# CS301_YOURGROUPNUM.net
KiCad netlist of a schematic drawn in Altium Designer
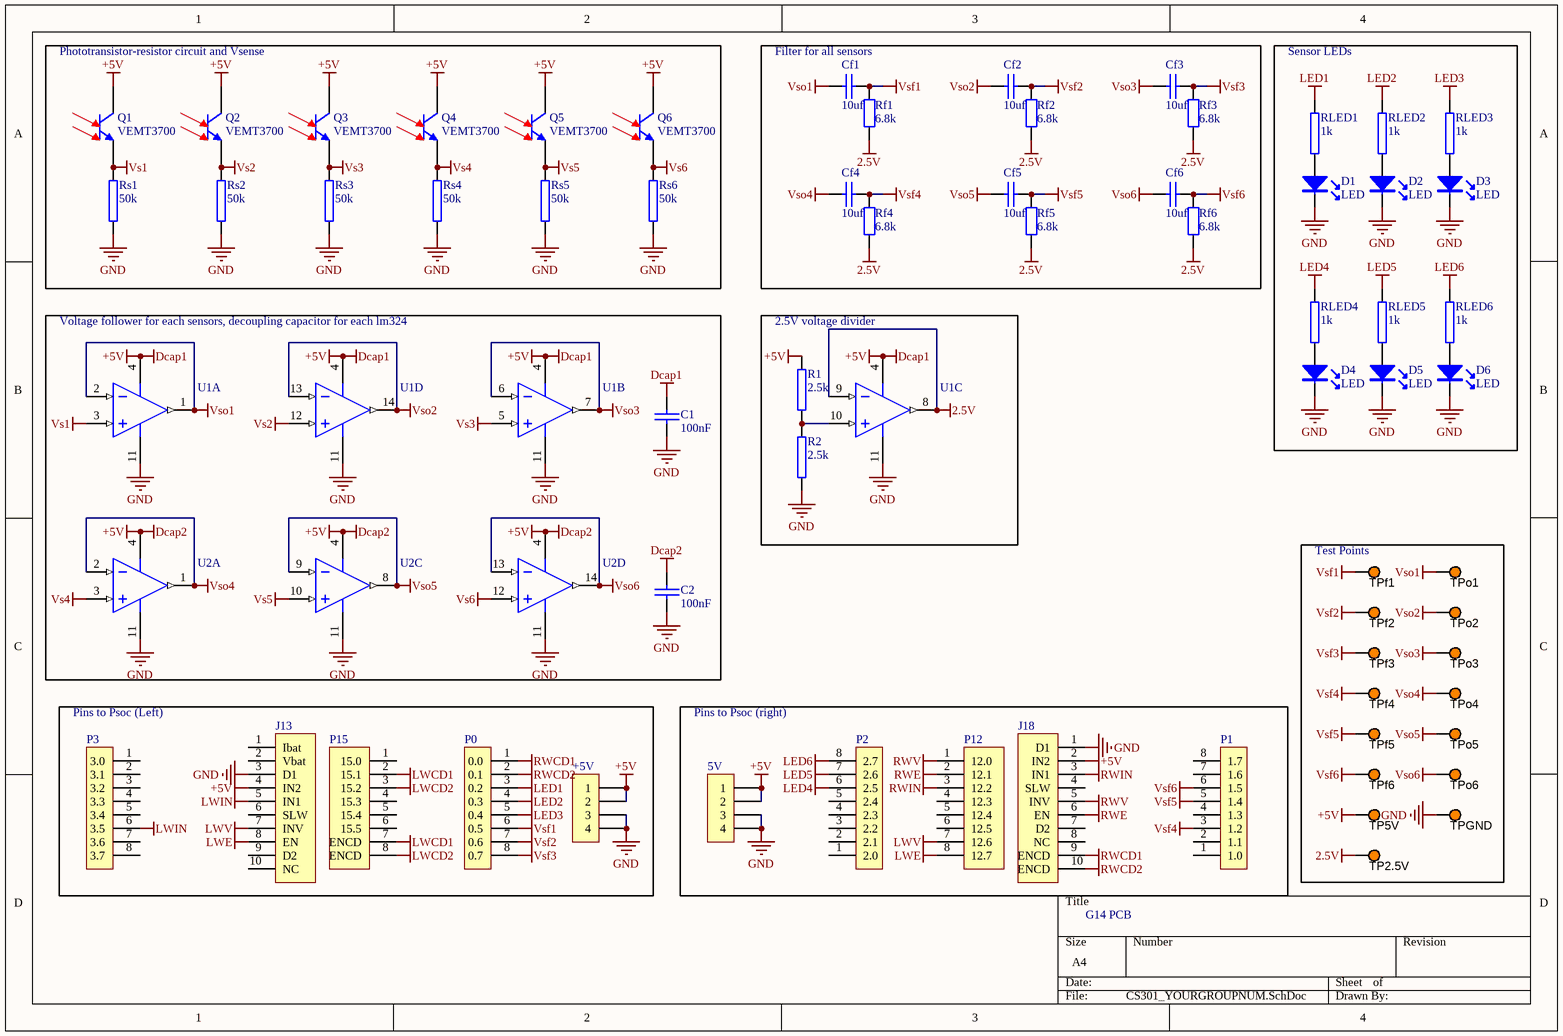
[diagram p0: CS301_YOURGROUPNUM.SchDoc]

(export (version "E")
  (design (tool "Eeschema 10.0.6"))
  (components
    (comp (ref "+5V")
      (value "5V")
      (footprint "IDC4")
      (description "Connector")
      (libsource (lib "Miscellaneous Devices") (part "CON4"))
    )
    (comp (ref "5V")
      (value "5V")
      (footprint "IDC4")
      (description "Connector")
      (libsource (lib "Miscellaneous Devices") (part "CON4"))
    )
    (comp (ref "C1")
      (value "100nF")
      (footprint "CCAP-5P0")
      (description "TH ceramic capacitor with 5mm pitch")
      (libsource (lib "EE209_SchLib") (part "CerCap_TH_5P0"))
    )
    (comp (ref "C2")
      (value "100nF")
      (footprint "CCAP-5P0")
      (description "TH ceramic capacitor with 5mm pitch")
      (libsource (lib "EE209_SchLib") (part "CerCap_TH_5P0"))
    )
    (comp (ref "Cf1")
      (value "10uf")
      (footprint "CCAP-5P0")
      (description "TH ceramic capacitor with 5mm pitch")
      (libsource (lib "EE209_SchLib") (part "CerCap_TH_5P0"))
    )
    (comp (ref "Cf2")
      (value "10uf")
      (footprint "CCAP-5P0")
      (description "TH ceramic capacitor with 5mm pitch")
      (libsource (lib "EE209_SchLib") (part "CerCap_TH_5P0"))
    )
    (comp (ref "Cf3")
      (value "10uf")
      (footprint "CCAP-5P0")
      (description "TH ceramic capacitor with 5mm pitch")
      (libsource (lib "EE209_SchLib") (part "CerCap_TH_5P0"))
    )
    (comp (ref "Cf4")
      (value "10uf")
      (footprint "CCAP-5P0")
      (description "TH ceramic capacitor with 5mm pitch")
      (libsource (lib "EE209_SchLib") (part "CerCap_TH_5P0"))
    )
    (comp (ref "Cf5")
      (value "10uf")
      (footprint "CCAP-5P0")
      (description "TH ceramic capacitor with 5mm pitch")
      (libsource (lib "EE209_SchLib") (part "CerCap_TH_5P0"))
    )
    (comp (ref "Cf6")
      (value "10uf")
      (footprint "CCAP-5P0")
      (description "TH ceramic capacitor with 5mm pitch")
      (libsource (lib "EE209_SchLib") (part "CerCap_TH_5P0"))
    )
    (comp (ref "D1") (value "LED") (footprint "LED0.1/5MM") (libsource (lib "COMSYS301") (part "LED")))
    (comp (ref "D2") (value "LED") (footprint "LED0.1/5MM") (libsource (lib "COMSYS301") (part "LED")))
    (comp (ref "D3") (value "LED") (footprint "LED0.1/5MM") (libsource (lib "COMSYS301") (part "LED")))
    (comp (ref "D4") (value "LED") (footprint "LED0.1/5MM") (libsource (lib "COMSYS301") (part "LED")))
    (comp (ref "D5") (value "LED") (footprint "LED0.1/5MM") (libsource (lib "COMSYS301") (part "LED")))
    (comp (ref "D6") (value "LED") (footprint "LED0.1/5MM") (libsource (lib "COMSYS301") (part "LED")))
    (comp (ref "J13")
      (value "CON10")
      (footprint "idc10")
      (description "Connector")
      (libsource (lib "Miscellaneous Devices") (part "CON10"))
    )
    (comp (ref "J18")
      (value "CON10")
      (footprint "IDC10")
      (description "Connector")
      (libsource (lib "") (part "CON10_1"))
    )
    (comp (ref "P0")
      (value "P0")
      (footprint "idc8")
      (description "Connector")
      (libsource (lib "") (part "CON8_2"))
    )
    (comp (ref "P1")
      (value "P1")
      (footprint "idc8")
      (description "Connector")
      (libsource (lib "") (part "CON8_1"))
    )
    (comp (ref "P2")
      (value "P2")
      (footprint "idc8")
      (description "Connector")
      (libsource (lib "Miscellaneous Devices") (part "CON8"))
    )
    (comp (ref "P3")
      (value "P3")
      (footprint "idc8")
      (description "Connector")
      (libsource (lib "") (part "CON8_2"))
    )
    (comp (ref "P12")
      (value "P12")
      (footprint "idc8")
      (description "Connector")
      (libsource (lib "Miscellaneous Devices") (part "CON8_1"))
    )
    (comp (ref "P15")
      (value "P15")
      (footprint "idc8")
      (description "Connector")
      (libsource (lib "") (part "CON8_1_1"))
    )
    (comp (ref "Q1")
      (value "VEMT3700")
      (footprint "VEMT3700")
      (description "Silicon NPN Phototransistor")
      (libsource (lib "COMSYS301") (part "VEMT3700"))
    )
    (comp (ref "Q2")
      (value "VEMT3700")
      (footprint "VEMT3700")
      (description "Silicon NPN Phototransistor")
      (libsource (lib "COMSYS301") (part "VEMT3700"))
    )
    (comp (ref "Q3")
      (value "VEMT3700")
      (footprint "VEMT3700")
      (description "Silicon NPN Phototransistor")
      (libsource (lib "COMSYS301") (part "VEMT3700"))
    )
    (comp (ref "Q4")
      (value "VEMT3700")
      (footprint "VEMT3700")
      (description "Silicon NPN Phototransistor")
      (libsource (lib "COMSYS301") (part "VEMT3700"))
    )
    (comp (ref "Q5")
      (value "VEMT3700")
      (footprint "VEMT3700")
      (description "Silicon NPN Phototransistor")
      (libsource (lib "COMSYS301") (part "VEMT3700"))
    )
    (comp (ref "Q6")
      (value "VEMT3700")
      (footprint "VEMT3700")
      (description "Silicon NPN Phototransistor")
      (libsource (lib "COMSYS301") (part "VEMT3700"))
    )
    (comp (ref "R1") (value "2.5k") (footprint "AXIAL0.4") (libsource (lib "COMSYS301") (part "RES2")))
    (comp (ref "R2") (value "2.5k") (footprint "AXIAL0.4") (libsource (lib "COMSYS301") (part "RES2")))
    (comp (ref "Rf1")
      (value "6.8k")
      (footprint "AXIAL-0.4")
      (description "Through hole resistor")
      (fields (field (name "PUBLISHER") "Altium Limited"))
      (libsource (lib "EE209_SchLib") (part "Res_TH_0AX4"))
    )
    (comp (ref "Rf2")
      (value "6.8k")
      (footprint "AXIAL-0.4")
      (description "Through hole resistor")
      (fields (field (name "PUBLISHER") "Altium Limited"))
      (libsource (lib "EE209_SchLib") (part "Res_TH_0AX4"))
    )
    (comp (ref "Rf3")
      (value "6.8k")
      (footprint "AXIAL-0.4")
      (description "Through hole resistor")
      (fields (field (name "PUBLISHER") "Altium Limited"))
      (libsource (lib "EE209_SchLib") (part "Res_TH_0AX4"))
    )
    (comp (ref "Rf4")
      (value "6.8k")
      (footprint "AXIAL-0.4")
      (description "Through hole resistor")
      (fields (field (name "PUBLISHER") "Altium Limited"))
      (libsource (lib "EE209_SchLib") (part "Res_TH_0AX4"))
    )
    (comp (ref "Rf5")
      (value "6.8k")
      (footprint "AXIAL-0.4")
      (description "Through hole resistor")
      (fields (field (name "PUBLISHER") "Altium Limited"))
      (libsource (lib "EE209_SchLib") (part "Res_TH_0AX4"))
    )
    (comp (ref "Rf6")
      (value "6.8k")
      (footprint "AXIAL-0.4")
      (description "Through hole resistor")
      (fields (field (name "PUBLISHER") "Altium Limited"))
      (libsource (lib "EE209_SchLib") (part "Res_TH_0AX4"))
    )
    (comp (ref "RLED1") (value "1k") (footprint "AXIAL0.4") (libsource (lib "COMSYS301") (part "RES2")))
    (comp (ref "RLED2") (value "1k") (footprint "AXIAL0.4") (libsource (lib "COMSYS301") (part "RES2")))
    (comp (ref "RLED3") (value "1k") (footprint "AXIAL0.4") (libsource (lib "COMSYS301") (part "RES2")))
    (comp (ref "RLED4") (value "1k") (footprint "AXIAL0.4") (libsource (lib "COMSYS301") (part "RES2")))
    (comp (ref "RLED5") (value "1k") (footprint "AXIAL0.4") (libsource (lib "COMSYS301") (part "RES2")))
    (comp (ref "RLED6") (value "1k") (footprint "AXIAL0.4") (libsource (lib "COMSYS301") (part "RES2")))
    (comp (ref "Rs1") (value "50k") (footprint "AXIAL0.4") (libsource (lib "COMSYS301") (part "RES2")))
    (comp (ref "Rs2") (value "50k") (footprint "AXIAL0.4") (libsource (lib "COMSYS301") (part "RES2")))
    (comp (ref "Rs3") (value "50k") (footprint "AXIAL0.4") (libsource (lib "COMSYS301") (part "RES2")))
    (comp (ref "Rs4") (value "50k") (footprint "AXIAL0.4") (libsource (lib "COMSYS301") (part "RES2")))
    (comp (ref "Rs5") (value "50k") (footprint "AXIAL0.4") (libsource (lib "COMSYS301") (part "RES2")))
    (comp (ref "Rs6") (value "50k") (footprint "AXIAL0.4") (libsource (lib "COMSYS301") (part "RES2")))
    (comp (ref "TP2.5V")
      (value "5003")
      (footprint "EE209_PcbLib:TP_TH")
      (description "Test Point, Orange, 1-Pin THD, RoHS")
      (libsource (lib "EE209_SchLib") (part "TestPoint"))
    )
    (comp (ref "TP5V")
      (value "5003")
      (footprint "EE209_PcbLib:TP_TH")
      (description "Test Point, Orange, 1-Pin THD, RoHS")
      (libsource (lib "EE209_SchLib") (part "TestPoint"))
    )
    (comp (ref "TPf1")
      (value "5003")
      (footprint "EE209_PcbLib:TP_TH")
      (description "Test Point, Orange, 1-Pin THD, RoHS")
      (libsource (lib "EE209_SchLib") (part "TestPoint"))
    )
    (comp (ref "TPf2")
      (value "5003")
      (footprint "EE209_PcbLib:TP_TH")
      (description "Test Point, Orange, 1-Pin THD, RoHS")
      (libsource (lib "EE209_SchLib") (part "TestPoint"))
    )
    (comp (ref "TPf3")
      (value "5003")
      (footprint "EE209_PcbLib:TP_TH")
      (description "Test Point, Orange, 1-Pin THD, RoHS")
      (libsource (lib "EE209_SchLib") (part "TestPoint"))
    )
    (comp (ref "TPf4")
      (value "5003")
      (footprint "EE209_PcbLib:TP_TH")
      (description "Test Point, Orange, 1-Pin THD, RoHS")
      (libsource (lib "EE209_SchLib") (part "TestPoint"))
    )
    (comp (ref "TPf5")
      (value "5003")
      (footprint "EE209_PcbLib:TP_TH")
      (description "Test Point, Orange, 1-Pin THD, RoHS")
      (libsource (lib "EE209_SchLib") (part "TestPoint"))
    )
    (comp (ref "TPf6")
      (value "5003")
      (footprint "EE209_PcbLib:TP_TH")
      (description "Test Point, Orange, 1-Pin THD, RoHS")
      (libsource (lib "EE209_SchLib") (part "TestPoint"))
    )
    (comp (ref "TPGND")
      (value "5003")
      (footprint "EE209_PcbLib:TP_TH")
      (description "Test Point, Orange, 1-Pin THD, RoHS")
      (libsource (lib "EE209_SchLib") (part "TestPoint"))
    )
    (comp (ref "TPo1")
      (value "5003")
      (footprint "EE209_PcbLib:TP_TH")
      (description "Test Point, Orange, 1-Pin THD, RoHS")
      (libsource (lib "EE209_SchLib") (part "TestPoint"))
    )
    (comp (ref "TPo2")
      (value "5003")
      (footprint "EE209_PcbLib:TP_TH")
      (description "Test Point, Orange, 1-Pin THD, RoHS")
      (libsource (lib "EE209_SchLib") (part "TestPoint"))
    )
    (comp (ref "TPo3")
      (value "5003")
      (footprint "EE209_PcbLib:TP_TH")
      (description "Test Point, Orange, 1-Pin THD, RoHS")
      (libsource (lib "EE209_SchLib") (part "TestPoint"))
    )
    (comp (ref "TPo4")
      (value "5003")
      (footprint "EE209_PcbLib:TP_TH")
      (description "Test Point, Orange, 1-Pin THD, RoHS")
      (libsource (lib "EE209_SchLib") (part "TestPoint"))
    )
    (comp (ref "TPo5")
      (value "5003")
      (footprint "EE209_PcbLib:TP_TH")
      (description "Test Point, Orange, 1-Pin THD, RoHS")
      (libsource (lib "EE209_SchLib") (part "TestPoint"))
    )
    (comp (ref "TPo6")
      (value "5003")
      (footprint "EE209_PcbLib:TP_TH")
      (description "Test Point, Orange, 1-Pin THD, RoHS")
      (libsource (lib "EE209_SchLib") (part "TestPoint"))
    )
    (comp (ref "U1")
      (value "LM324")
      (footprint "DIP-14")
      (description "IC OPAMP GP 14DIP")
      (fields
        (field (name "MANUFACTURER") "ON Semiconductor")
        (field (name "MANUFACTURER PART NUMBER") "LM324N")
      )
      (libsource (lib "EE209_SchLib") (part "LM324N_TH_DIP16"))
    )
    (comp (ref "U2")
      (value "LM324")
      (footprint "DIP-14")
      (description "IC OPAMP GP 14DIP")
      (fields
        (field (name "MANUFACTURER") "ON Semiconductor")
        (field (name "MANUFACTURER PART NUMBER") "LM324N")
      )
      (libsource (lib "EE209_SchLib") (part "LM324N_TH_DIP16"))
    )
  )
  (nets
    (net (code "1") (name "+5V") (class "Default")
      (node (ref "+5V") (pin "1") (pinfunction "1_1") (pintype "passive"))
      (node (ref "+5V") (pin "2") (pinfunction "2_2") (pintype "passive"))
      (node (ref "5V") (pin "1") (pinfunction "1_1") (pintype "passive"))
      (node (ref "5V") (pin "2") (pinfunction "2_2") (pintype "passive"))
      (node (ref "C1") (pin "1") (pinfunction "1_1") (pintype "passive"))
      (node (ref "C2") (pin "1") (pinfunction "1_1") (pintype "passive"))
      (node (ref "J13") (pin "4") (pinfunction "IN2_4") (pintype "passive"))
      (node (ref "J18") (pin "2") (pinfunction "IN2_2") (pintype "passive"))
      (node (ref "Q1") (pin "1") (pinfunction "C_1") (pintype "passive"))
      (node (ref "Q2") (pin "1") (pinfunction "C_1") (pintype "passive"))
      (node (ref "Q3") (pin "1") (pinfunction "C_1") (pintype "passive"))
      (node (ref "Q4") (pin "1") (pinfunction "C_1") (pintype "passive"))
      (node (ref "Q5") (pin "1") (pinfunction "C_1") (pintype "passive"))
      (node (ref "Q6") (pin "1") (pinfunction "C_1") (pintype "passive"))
      (node (ref "R1") (pin "1") (pinfunction "1_1") (pintype "passive"))
      (node (ref "TP5V") (pin "1") (pinfunction "1_1") (pintype "passive"))
      (node (ref "U1") (pin "4") (pinfunction "VDD_4") (pintype "power_in"))
      (node (ref "U2") (pin "4") (pinfunction "VDD_4") (pintype "power_in"))
    )
    (net (code "2") (name "2.5V") (class "Default")
      (node (ref "Rf1") (pin "1") (pinfunction "1_1") (pintype "passive"))
      (node (ref "Rf2") (pin "1") (pinfunction "1_1") (pintype "passive"))
      (node (ref "Rf3") (pin "1") (pinfunction "1_1") (pintype "passive"))
      (node (ref "Rf4") (pin "1") (pinfunction "1_1") (pintype "passive"))
      (node (ref "Rf5") (pin "1") (pinfunction "1_1") (pintype "passive"))
      (node (ref "Rf6") (pin "1") (pinfunction "1_1") (pintype "passive"))
      (node (ref "TP2.5V") (pin "1") (pinfunction "1_1") (pintype "passive"))
      (node (ref "U1") (pin "8") (pinfunction "VOUTC_8") (pintype "output"))
      (node (ref "U1") (pin "9") (pinfunction "VINC-_9") (pintype "input"))
    )
    (net (code "3") (name "GND") (class "Default")
      (node (ref "+5V") (pin "3") (pinfunction "3_3") (pintype "passive"))
      (node (ref "+5V") (pin "4") (pinfunction "4_4") (pintype "passive"))
      (node (ref "5V") (pin "3") (pinfunction "3_3") (pintype "passive"))
      (node (ref "5V") (pin "4") (pinfunction "4_4") (pintype "passive"))
      (node (ref "C1") (pin "2") (pinfunction "2_2") (pintype "passive"))
      (node (ref "C2") (pin "2") (pinfunction "2_2") (pintype "passive"))
      (node (ref "D1") (pin "K") (pinfunction "2_K") (pintype "passive"))
      (node (ref "D2") (pin "K") (pinfunction "2_K") (pintype "passive"))
      (node (ref "D3") (pin "K") (pinfunction "2_K") (pintype "passive"))
      (node (ref "D4") (pin "K") (pinfunction "2_K") (pintype "passive"))
      (node (ref "D5") (pin "K") (pinfunction "2_K") (pintype "passive"))
      (node (ref "D6") (pin "K") (pinfunction "2_K") (pintype "passive"))
      (node (ref "J13") (pin "3") (pinfunction "D1_3") (pintype "passive"))
      (node (ref "J18") (pin "1") (pinfunction "D1_1") (pintype "passive"))
      (node (ref "R2") (pin "2") (pinfunction "2_2") (pintype "passive"))
      (node (ref "Rs1") (pin "2") (pinfunction "2_2") (pintype "passive"))
      (node (ref "Rs2") (pin "2") (pinfunction "2_2") (pintype "passive"))
      (node (ref "Rs3") (pin "2") (pinfunction "2_2") (pintype "passive"))
      (node (ref "Rs4") (pin "2") (pinfunction "2_2") (pintype "passive"))
      (node (ref "Rs5") (pin "2") (pinfunction "2_2") (pintype "passive"))
      (node (ref "Rs6") (pin "2") (pinfunction "2_2") (pintype "passive"))
      (node (ref "TPGND") (pin "1") (pinfunction "1_1") (pintype "passive"))
      (node (ref "U1") (pin "11") (pinfunction "VSS_11") (pintype "power_in"))
      (node (ref "U2") (pin "11") (pinfunction "VSS_11") (pintype "power_in"))
    )
    (net (code "4") (name "LED1") (class "Default")
      (node (ref "P0") (pin "3") (pinfunction "3.2_3") (pintype "passive"))
      (node (ref "RLED1") (pin "1") (pinfunction "1_1") (pintype "passive"))
    )
    (net (code "5") (name "LED2") (class "Default")
      (node (ref "P0") (pin "4") (pinfunction "3.3_4") (pintype "passive"))
      (node (ref "RLED2") (pin "1") (pinfunction "1_1") (pintype "passive"))
    )
    (net (code "6") (name "LED3") (class "Default")
      (node (ref "P0") (pin "5") (pinfunction "3.4_5") (pintype "passive"))
      (node (ref "RLED3") (pin "1") (pinfunction "1_1") (pintype "passive"))
    )
    (net (code "7") (name "LED4") (class "Default")
      (node (ref "P2") (pin "6") (pinfunction "2.5_6") (pintype "passive"))
      (node (ref "RLED4") (pin "1") (pinfunction "1_1") (pintype "passive"))
    )
    (net (code "8") (name "LED5") (class "Default")
      (node (ref "P2") (pin "7") (pinfunction "2.6_7") (pintype "passive"))
      (node (ref "RLED5") (pin "1") (pinfunction "1_1") (pintype "passive"))
    )
    (net (code "9") (name "LED6") (class "Default")
      (node (ref "P2") (pin "8") (pinfunction "2.7_8") (pintype "passive"))
      (node (ref "RLED6") (pin "1") (pinfunction "1_1") (pintype "passive"))
    )
    (net (code "10") (name "LWCD1") (class "Default")
      (node (ref "P15") (pin "2") (pinfunction "15.1_2") (pintype "passive"))
      (node (ref "P15") (pin "7") (pinfunction "ENCD_7") (pintype "passive"))
    )
    (net (code "11") (name "LWCD2") (class "Default")
      (node (ref "P15") (pin "3") (pinfunction "15.2_3") (pintype "passive"))
      (node (ref "P15") (pin "8") (pinfunction "ENCD_8") (pintype "passive"))
    )
    (net (code "12") (name "LWE") (class "Default")
      (node (ref "J13") (pin "8") (pinfunction "EN_8") (pintype "passive"))
      (node (ref "P12") (pin "8") (pinfunction "12.7_8") (pintype "passive"))
    )
    (net (code "13") (name "LWIN") (class "Default")
      (node (ref "J13") (pin "5") (pinfunction "IN1_5") (pintype "passive"))
      (node (ref "P3") (pin "6") (pinfunction "3.5_6") (pintype "passive"))
    )
    (net (code "14") (name "LWV") (class "Default")
      (node (ref "J13") (pin "7") (pinfunction "INV_7") (pintype "passive"))
      (node (ref "P12") (pin "7") (pinfunction "12.6_7") (pintype "passive"))
    )
    (net (code "15") (name "Net-(D1-1)") (class "Default")
      (node (ref "D1") (pin "A") (pinfunction "1_A") (pintype "passive"))
      (node (ref "RLED1") (pin "2") (pinfunction "2_2") (pintype "passive"))
    )
    (net (code "16") (name "Net-(D2-1)") (class "Default")
      (node (ref "D2") (pin "A") (pinfunction "1_A") (pintype "passive"))
      (node (ref "RLED2") (pin "2") (pinfunction "2_2") (pintype "passive"))
    )
    (net (code "17") (name "Net-(D3-1)") (class "Default")
      (node (ref "D3") (pin "A") (pinfunction "1_A") (pintype "passive"))
      (node (ref "RLED3") (pin "2") (pinfunction "2_2") (pintype "passive"))
    )
    (net (code "18") (name "Net-(D4-1)") (class "Default")
      (node (ref "D4") (pin "A") (pinfunction "1_A") (pintype "passive"))
      (node (ref "RLED4") (pin "2") (pinfunction "2_2") (pintype "passive"))
    )
    (net (code "19") (name "Net-(D5-1)") (class "Default")
      (node (ref "D5") (pin "A") (pinfunction "1_A") (pintype "passive"))
      (node (ref "RLED5") (pin "2") (pinfunction "2_2") (pintype "passive"))
    )
    (net (code "20") (name "Net-(D6-1)") (class "Default")
      (node (ref "D6") (pin "A") (pinfunction "1_A") (pintype "passive"))
      (node (ref "RLED6") (pin "2") (pinfunction "2_2") (pintype "passive"))
    )
    (net (code "21") (name "Net-(U1C-VINC+)") (class "Default")
      (node (ref "R1") (pin "2") (pinfunction "2_2") (pintype "passive"))
      (node (ref "R2") (pin "1") (pinfunction "1_1") (pintype "passive"))
      (node (ref "U1") (pin "10") (pinfunction "VINC+_10") (pintype "input"))
    )
    (net (code "22") (name "RWCD1") (class "Default")
      (node (ref "J18") (pin "9") (pinfunction "ENCD_9") (pintype "passive"))
      (node (ref "P0") (pin "1") (pinfunction "3.0_1") (pintype "passive"))
    )
    (net (code "23") (name "RWCD2") (class "Default")
      (node (ref "J18") (pin "10") (pinfunction "ENCD_10") (pintype "passive"))
      (node (ref "P0") (pin "2") (pinfunction "3.1_2") (pintype "passive"))
    )
    (net (code "24") (name "RWE") (class "Default")
      (node (ref "J18") (pin "6") (pinfunction "EN_6") (pintype "passive"))
      (node (ref "P12") (pin "2") (pinfunction "12.1_2") (pintype "passive"))
    )
    (net (code "25") (name "RWIN") (class "Default")
      (node (ref "J18") (pin "3") (pinfunction "IN1_3") (pintype "passive"))
      (node (ref "P12") (pin "3") (pinfunction "12.2_3") (pintype "passive"))
    )
    (net (code "26") (name "RWV") (class "Default")
      (node (ref "J18") (pin "5") (pinfunction "INV_5") (pintype "passive"))
      (node (ref "P12") (pin "1") (pinfunction "12.0_1") (pintype "passive"))
    )
    (net (code "27") (name "Vs1") (class "Default")
      (node (ref "Q1") (pin "2") (pinfunction "E_2") (pintype "passive"))
      (node (ref "Rs1") (pin "1") (pinfunction "1_1") (pintype "passive"))
      (node (ref "U1") (pin "3") (pinfunction "VINA+_3") (pintype "input"))
    )
    (net (code "28") (name "Vs2") (class "Default")
      (node (ref "Q2") (pin "2") (pinfunction "E_2") (pintype "passive"))
      (node (ref "Rs2") (pin "1") (pinfunction "1_1") (pintype "passive"))
      (node (ref "U1") (pin "12") (pinfunction "VIND+_12") (pintype "input"))
    )
    (net (code "29") (name "Vs3") (class "Default")
      (node (ref "Q3") (pin "2") (pinfunction "E_2") (pintype "passive"))
      (node (ref "Rs3") (pin "1") (pinfunction "1_1") (pintype "passive"))
      (node (ref "U1") (pin "5") (pinfunction "VINB+_5") (pintype "input"))
    )
    (net (code "30") (name "Vs4") (class "Default")
      (node (ref "Q4") (pin "2") (pinfunction "E_2") (pintype "passive"))
      (node (ref "Rs4") (pin "1") (pinfunction "1_1") (pintype "passive"))
      (node (ref "U2") (pin "3") (pinfunction "VINA+_3") (pintype "input"))
    )
    (net (code "31") (name "Vs5") (class "Default")
      (node (ref "Q5") (pin "2") (pinfunction "E_2") (pintype "passive"))
      (node (ref "Rs5") (pin "1") (pinfunction "1_1") (pintype "passive"))
      (node (ref "U2") (pin "10") (pinfunction "VINC+_10") (pintype "input"))
    )
    (net (code "32") (name "Vs6") (class "Default")
      (node (ref "Q6") (pin "2") (pinfunction "E_2") (pintype "passive"))
      (node (ref "Rs6") (pin "1") (pinfunction "1_1") (pintype "passive"))
      (node (ref "U2") (pin "12") (pinfunction "VIND+_12") (pintype "input"))
    )
    (net (code "33") (name "Vsf1") (class "Default")
      (node (ref "Cf1") (pin "2") (pinfunction "2_2") (pintype "passive"))
      (node (ref "P0") (pin "6") (pinfunction "3.5_6") (pintype "passive"))
      (node (ref "Rf1") (pin "2") (pinfunction "2_2") (pintype "passive"))
      (node (ref "TPf1") (pin "1") (pinfunction "1_1") (pintype "passive"))
    )
    (net (code "34") (name "Vsf2") (class "Default")
      (node (ref "Cf2") (pin "2") (pinfunction "2_2") (pintype "passive"))
      (node (ref "P0") (pin "7") (pinfunction "3.6_7") (pintype "passive"))
      (node (ref "Rf2") (pin "2") (pinfunction "2_2") (pintype "passive"))
      (node (ref "TPf2") (pin "1") (pinfunction "1_1") (pintype "passive"))
    )
    (net (code "35") (name "Vsf3") (class "Default")
      (node (ref "Cf3") (pin "2") (pinfunction "2_2") (pintype "passive"))
      (node (ref "P0") (pin "8") (pinfunction "3.7_8") (pintype "passive"))
      (node (ref "Rf3") (pin "2") (pinfunction "2_2") (pintype "passive"))
      (node (ref "TPf3") (pin "1") (pinfunction "1_1") (pintype "passive"))
    )
    (net (code "36") (name "Vsf4") (class "Default")
      (node (ref "Cf4") (pin "2") (pinfunction "2_2") (pintype "passive"))
      (node (ref "P1") (pin "3") (pinfunction "1.2_3") (pintype "passive"))
      (node (ref "Rf4") (pin "2") (pinfunction "2_2") (pintype "passive"))
      (node (ref "TPf4") (pin "1") (pinfunction "1_1") (pintype "passive"))
    )
    (net (code "37") (name "Vsf5") (class "Default")
      (node (ref "Cf5") (pin "2") (pinfunction "2_2") (pintype "passive"))
      (node (ref "P1") (pin "5") (pinfunction "1.4_5") (pintype "passive"))
      (node (ref "Rf5") (pin "2") (pinfunction "2_2") (pintype "passive"))
      (node (ref "TPf5") (pin "1") (pinfunction "1_1") (pintype "passive"))
    )
    (net (code "38") (name "Vsf6") (class "Default")
      (node (ref "Cf6") (pin "2") (pinfunction "2_2") (pintype "passive"))
      (node (ref "P1") (pin "6") (pinfunction "1.5_6") (pintype "passive"))
      (node (ref "Rf6") (pin "2") (pinfunction "2_2") (pintype "passive"))
      (node (ref "TPf6") (pin "1") (pinfunction "1_1") (pintype "passive"))
    )
    (net (code "39") (name "Vso1") (class "Default")
      (node (ref "Cf1") (pin "1") (pinfunction "1_1") (pintype "passive"))
      (node (ref "TPo1") (pin "1") (pinfunction "1_1") (pintype "passive"))
      (node (ref "U1") (pin "1") (pinfunction "VOUTA_1") (pintype "output"))
      (node (ref "U1") (pin "2") (pinfunction "VINA-_2") (pintype "input"))
    )
    (net (code "40") (name "Vso2") (class "Default")
      (node (ref "Cf2") (pin "1") (pinfunction "1_1") (pintype "passive"))
      (node (ref "TPo2") (pin "1") (pinfunction "1_1") (pintype "passive"))
      (node (ref "U1") (pin "13") (pinfunction "VIND-_13") (pintype "input"))
      (node (ref "U1") (pin "14") (pinfunction "VOUTD_14") (pintype "output"))
    )
    (net (code "41") (name "Vso3") (class "Default")
      (node (ref "Cf3") (pin "1") (pinfunction "1_1") (pintype "passive"))
      (node (ref "TPo3") (pin "1") (pinfunction "1_1") (pintype "passive"))
      (node (ref "U1") (pin "6") (pinfunction "VINB-_6") (pintype "input"))
      (node (ref "U1") (pin "7") (pinfunction "VOUTB_7") (pintype "output"))
    )
    (net (code "42") (name "Vso4") (class "Default")
      (node (ref "Cf4") (pin "1") (pinfunction "1_1") (pintype "passive"))
      (node (ref "TPo4") (pin "1") (pinfunction "1_1") (pintype "passive"))
      (node (ref "U2") (pin "1") (pinfunction "VOUTA_1") (pintype "output"))
      (node (ref "U2") (pin "2") (pinfunction "VINA-_2") (pintype "input"))
    )
    (net (code "43") (name "Vso5") (class "Default")
      (node (ref "Cf5") (pin "1") (pinfunction "1_1") (pintype "passive"))
      (node (ref "TPo5") (pin "1") (pinfunction "1_1") (pintype "passive"))
      (node (ref "U2") (pin "8") (pinfunction "VOUTC_8") (pintype "output"))
      (node (ref "U2") (pin "9") (pinfunction "VINC-_9") (pintype "input"))
    )
    (net (code "44") (name "Vso6") (class "Default")
      (node (ref "Cf6") (pin "1") (pinfunction "1_1") (pintype "passive"))
      (node (ref "TPo6") (pin "1") (pinfunction "1_1") (pintype "passive"))
      (node (ref "U2") (pin "13") (pinfunction "VIND-_13") (pintype "input"))
      (node (ref "U2") (pin "14") (pinfunction "VOUTD_14") (pintype "output"))
    )
    (net (code "45") (name "unconnected-(J13-D2-Pad9)") (class "Default")
      (node (ref "J13") (pin "9") (pinfunction "D2_9") (pintype "passive"))
    )
    (net (code "46") (name "unconnected-(J13-Ibat-Pad1)") (class "Default")
      (node (ref "J13") (pin "1") (pinfunction "Ibat_1") (pintype "passive"))
    )
    (net (code "47") (name "unconnected-(J13-NC-Pad10)") (class "Default")
      (node (ref "J13") (pin "10") (pinfunction "NC_10") (pintype "passive"))
    )
    (net (code "48") (name "unconnected-(J13-SLW-Pad6)") (class "Default")
      (node (ref "J13") (pin "6") (pinfunction "SLW_6") (pintype "passive"))
    )
    (net (code "49") (name "unconnected-(J13-Vbat-Pad2)") (class "Default")
      (node (ref "J13") (pin "2") (pinfunction "Vbat_2") (pintype "passive"))
    )
    (net (code "50") (name "unconnected-(J18-D2-Pad7)") (class "Default")
      (node (ref "J18") (pin "7") (pinfunction "D2_7") (pintype "passive"))
    )
    (net (code "51") (name "unconnected-(J18-NC-Pad8)") (class "Default")
      (node (ref "J18") (pin "8") (pinfunction "NC_8") (pintype "passive"))
    )
    (net (code "52") (name "unconnected-(J18-SLW-Pad4)") (class "Default")
      (node (ref "J18") (pin "4") (pinfunction "SLW_4") (pintype "passive"))
    )
    (net (code "53") (name "unconnected-(P1-1.0-Pad1)") (class "Default")
      (node (ref "P1") (pin "1") (pinfunction "1.0_1") (pintype "passive"))
    )
    (net (code "54") (name "unconnected-(P1-1.1-Pad2)") (class "Default")
      (node (ref "P1") (pin "2") (pinfunction "1.1_2") (pintype "passive"))
    )
    (net (code "55") (name "unconnected-(P1-1.3-Pad4)") (class "Default")
      (node (ref "P1") (pin "4") (pinfunction "1.3_4") (pintype "passive"))
    )
    (net (code "56") (name "unconnected-(P1-1.6-Pad7)") (class "Default")
      (node (ref "P1") (pin "7") (pinfunction "1.6_7") (pintype "passive"))
    )
    (net (code "57") (name "unconnected-(P1-1.7-Pad8)") (class "Default")
      (node (ref "P1") (pin "8") (pinfunction "1.7_8") (pintype "passive"))
    )
    (net (code "58") (name "unconnected-(P2-2.0-Pad1)") (class "Default")
      (node (ref "P2") (pin "1") (pinfunction "2.0_1") (pintype "passive"))
    )
    (net (code "59") (name "unconnected-(P2-2.1-Pad2)") (class "Default")
      (node (ref "P2") (pin "2") (pinfunction "2.1_2") (pintype "passive"))
    )
    (net (code "60") (name "unconnected-(P2-2.2-Pad3)") (class "Default")
      (node (ref "P2") (pin "3") (pinfunction "2.2_3") (pintype "passive"))
    )
    (net (code "61") (name "unconnected-(P2-2.3-Pad4)") (class "Default")
      (node (ref "P2") (pin "4") (pinfunction "2.3_4") (pintype "passive"))
    )
    (net (code "62") (name "unconnected-(P2-2.4-Pad5)") (class "Default")
      (node (ref "P2") (pin "5") (pinfunction "2.4_5") (pintype "passive"))
    )
    (net (code "63") (name "unconnected-(P3-3.0-Pad1)") (class "Default")
      (node (ref "P3") (pin "1") (pinfunction "3.0_1") (pintype "passive"))
    )
    (net (code "64") (name "unconnected-(P3-3.1-Pad2)") (class "Default")
      (node (ref "P3") (pin "2") (pinfunction "3.1_2") (pintype "passive"))
    )
    (net (code "65") (name "unconnected-(P3-3.2-Pad3)") (class "Default")
      (node (ref "P3") (pin "3") (pinfunction "3.2_3") (pintype "passive"))
    )
    (net (code "66") (name "unconnected-(P3-3.3-Pad4)") (class "Default")
      (node (ref "P3") (pin "4") (pinfunction "3.3_4") (pintype "passive"))
    )
    (net (code "67") (name "unconnected-(P3-3.4-Pad5)") (class "Default")
      (node (ref "P3") (pin "5") (pinfunction "3.4_5") (pintype "passive"))
    )
    (net (code "68") (name "unconnected-(P3-3.6-Pad7)") (class "Default")
      (node (ref "P3") (pin "7") (pinfunction "3.6_7") (pintype "passive"))
    )
    (net (code "69") (name "unconnected-(P3-3.7-Pad8)") (class "Default")
      (node (ref "P3") (pin "8") (pinfunction "3.7_8") (pintype "passive"))
    )
    (net (code "70") (name "unconnected-(P12-12.3-Pad4)") (class "Default")
      (node (ref "P12") (pin "4") (pinfunction "12.3_4") (pintype "passive"))
    )
    (net (code "71") (name "unconnected-(P12-12.4-Pad5)") (class "Default")
      (node (ref "P12") (pin "5") (pinfunction "12.4_5") (pintype "passive"))
    )
    (net (code "72") (name "unconnected-(P12-12.5-Pad6)") (class "Default")
      (node (ref "P12") (pin "6") (pinfunction "12.5_6") (pintype "passive"))
    )
    (net (code "73") (name "unconnected-(P15-15.0-Pad1)") (class "Default")
      (node (ref "P15") (pin "1") (pinfunction "15.0_1") (pintype "passive"))
    )
    (net (code "74") (name "unconnected-(P15-15.3-Pad4)") (class "Default")
      (node (ref "P15") (pin "4") (pinfunction "15.3_4") (pintype "passive"))
    )
    (net (code "75") (name "unconnected-(P15-15.4-Pad5)") (class "Default")
      (node (ref "P15") (pin "5") (pinfunction "15.4_5") (pintype "passive"))
    )
    (net (code "76") (name "unconnected-(P15-15.5-Pad6)") (class "Default")
      (node (ref "P15") (pin "6") (pinfunction "15.5_6") (pintype "passive"))
    )
  )
)
